# shrew-mini.net
KiCad netlist of a schematic drawn in EAGLE
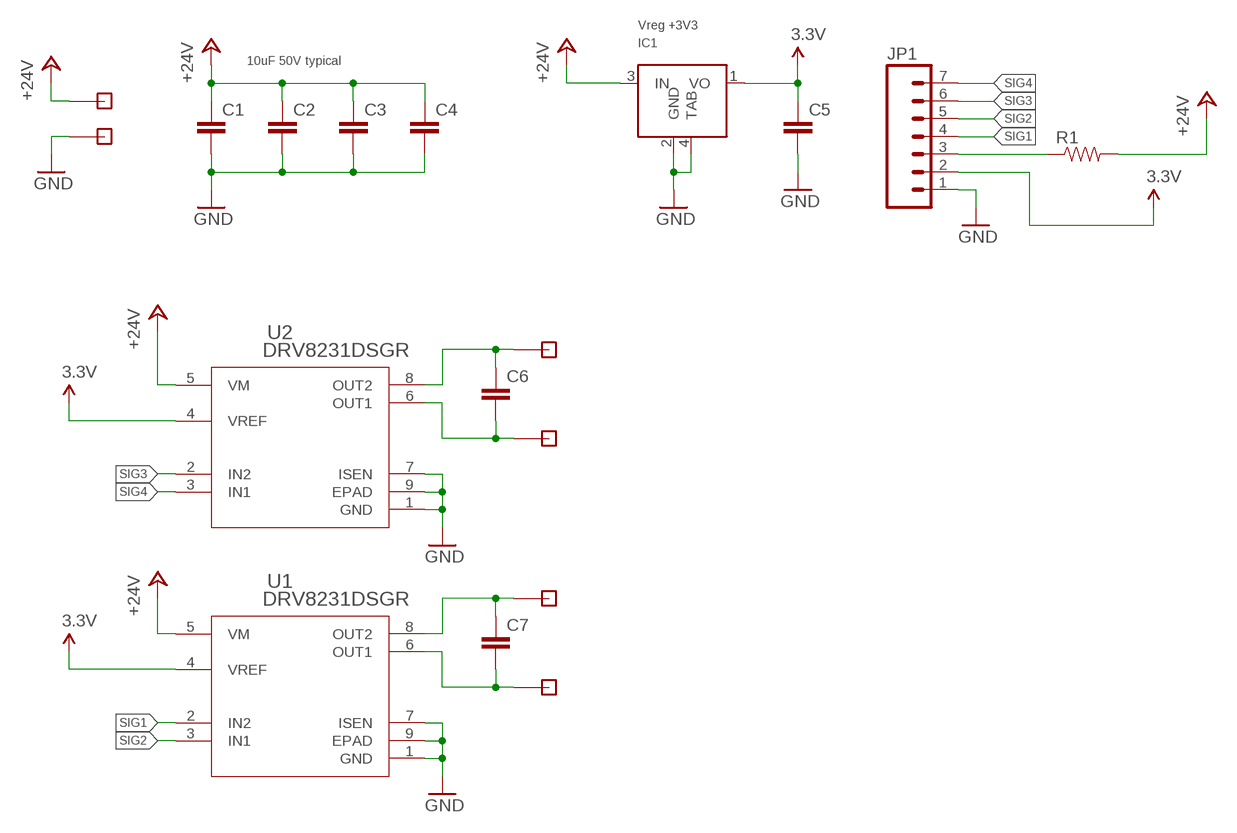
[diagram p0: schematic, sheet 1]

(export (version "E")
  (design (tool "Eeschema 10.0.6"))
  (components
    (comp (ref "C1")
      (value "CAP0805")
      (footprint "eagle-import:0805")
      (libsource (lib "eagle-import") (part "CAP0805"))
    )
    (comp (ref "C2")
      (value "CAP0805")
      (footprint "eagle-import:0805")
      (libsource (lib "eagle-import") (part "CAP0805"))
    )
    (comp (ref "C3")
      (value "CAP0805")
      (footprint "eagle-import:0805")
      (libsource (lib "eagle-import") (part "CAP0805"))
    )
    (comp (ref "C4")
      (value "CAP0805")
      (footprint "eagle-import:0805")
      (libsource (lib "eagle-import") (part "CAP0805"))
    )
    (comp (ref "C5")
      (value "CAP0805")
      (footprint "eagle-import:0805")
      (libsource (lib "eagle-import") (part "CAP0805"))
    )
    (comp (ref "C6")
      (value "CAP0402-CAP")
      (footprint "eagle-import:0402-CAP")
      (libsource (lib "eagle-import") (part "CAP0402-CAP"))
    )
    (comp (ref "C7")
      (value "CAP0402-CAP")
      (footprint "eagle-import:0402-CAP")
      (libsource (lib "eagle-import") (part "CAP0402-CAP"))
    )
    (comp (ref "IC1")
      (value "Vreg +3V3")
      (footprint "eagle-import:SOT89")
      (libsource (lib "eagle-import") (part "V_REG_SOT89-SOT89"))
    )
    (comp (ref "JP1")
      (value "M07-2MM-TH")
      (footprint "eagle-import:1X07-2MM-TH")
      (libsource (lib "eagle-import") (part "M07-2MM-TH"))
    )
    (comp (ref "R1")
      (value "RESISTOR0402-RES")
      (footprint "eagle-import:0402-RES")
      (libsource (lib "eagle-import") (part "RESISTOR0402-RES"))
    )
    (comp (ref "U1")
      (value "DRV8231DSGR")
      (footprint "eagle-import:WSON8_DRV8231_TEX")
      (fields (field (name "COPYRIGHT") "Copyright (C) 2024 Ultra Librarian. All rights reserved."))
      (libsource (lib "eagle-import") (part "DRV8231DSGR"))
    )
    (comp (ref "U2")
      (value "DRV8231DSGR")
      (footprint "eagle-import:WSON8_DRV8231_TEX")
      (fields (field (name "COPYRIGHT") "Copyright (C) 2024 Ultra Librarian. All rights reserved."))
      (libsource (lib "eagle-import") (part "DRV8231DSGR"))
    )
    (comp (ref "X1")
      (value "PIN-1X-BIG")
      (footprint "eagle-import:PAD-1X-BIG")
      (libsource (lib "eagle-import") (part "PIN-1X-BIG"))
    )
    (comp (ref "X2")
      (value "PIN-1X-BIG")
      (footprint "eagle-import:PAD-1X-BIG")
      (libsource (lib "eagle-import") (part "PIN-1X-BIG"))
    )
    (comp (ref "X3")
      (value "PIN-1X-BIG")
      (footprint "eagle-import:PAD-1X-BIG")
      (libsource (lib "eagle-import") (part "PIN-1X-BIG"))
    )
    (comp (ref "X4")
      (value "PIN-1X-BIG")
      (footprint "eagle-import:PAD-1X-BIG")
      (libsource (lib "eagle-import") (part "PIN-1X-BIG"))
    )
    (comp (ref "X5")
      (value "PIN-1X-1.5MMSQ")
      (footprint "eagle-import:PAD-1X-1.5MMSQ")
      (libsource (lib "eagle-import") (part "PIN-1X-1.5MMSQ"))
    )
    (comp (ref "X6")
      (value "PIN-1X-MED")
      (footprint "eagle-import:PAD-1X-MED")
      (libsource (lib "eagle-import") (part "PIN-1X-MED"))
    )
  )
  (nets
    (net (code "1") (name "+24V") (class "Default")
      (node (ref "C1") (pin "1") (pinfunction "1_1") (pintype "passive"))
      (node (ref "C2") (pin "1") (pinfunction "1_1") (pintype "passive"))
      (node (ref "C3") (pin "1") (pinfunction "1_1") (pintype "passive"))
      (node (ref "C4") (pin "1") (pinfunction "1_1") (pintype "passive"))
      (node (ref "IC1") (pin "3") (pinfunction "IN_3") (pintype "input"))
      (node (ref "R1") (pin "2") (pinfunction "2_2") (pintype "passive"))
      (node (ref "U1") (pin "5") (pinfunction "VM_5") (pintype "input"))
      (node (ref "U2") (pin "5") (pinfunction "VM_5") (pintype "input"))
      (node (ref "X5") (pin "P$1") (pinfunction "P$1_P$1") (pintype "bidirectional"))
    )
    (net (code "2") (name "3.3V") (class "Default")
      (node (ref "C5") (pin "1") (pinfunction "1_1") (pintype "passive"))
      (node (ref "IC1") (pin "1") (pinfunction "VO_1") (pintype "output"))
      (node (ref "JP1") (pin "2") (pinfunction "2_2") (pintype "passive"))
      (node (ref "U1") (pin "4") (pinfunction "VREF_4") (pintype "input"))
      (node (ref "U2") (pin "4") (pinfunction "VREF_4") (pintype "input"))
    )
    (net (code "3") (name "GND") (class "Default")
      (node (ref "C1") (pin "2") (pinfunction "2_2") (pintype "passive"))
      (node (ref "C2") (pin "2") (pinfunction "2_2") (pintype "passive"))
      (node (ref "C3") (pin "2") (pinfunction "2_2") (pintype "passive"))
      (node (ref "C4") (pin "2") (pinfunction "2_2") (pintype "passive"))
      (node (ref "C5") (pin "2") (pinfunction "2_2") (pintype "passive"))
      (node (ref "IC1") (pin "2") (pinfunction "GND_2") (pintype "input"))
      (node (ref "IC1") (pin "4") (pinfunction "TAB_4") (pintype "input"))
      (node (ref "JP1") (pin "1") (pinfunction "1_1") (pintype "passive"))
      (node (ref "U1") (pin "1") (pinfunction "GND_1") (pintype "input"))
      (node (ref "U1") (pin "7") (pinfunction "ISEN_7") (pintype "input"))
      (node (ref "U1") (pin "9") (pinfunction "EPAD_9") (pintype "input"))
      (node (ref "U2") (pin "1") (pinfunction "GND_1") (pintype "input"))
      (node (ref "U2") (pin "7") (pinfunction "ISEN_7") (pintype "input"))
      (node (ref "U2") (pin "9") (pinfunction "EPAD_9") (pintype "input"))
      (node (ref "X6") (pin "P$1") (pinfunction "P$1_P$1") (pintype "bidirectional"))
    )
    (net (code "4") (name "Net-(JP1-Pad3)") (class "Default")
      (node (ref "JP1") (pin "3") (pinfunction "3_3") (pintype "passive"))
      (node (ref "R1") (pin "1") (pinfunction "1_1") (pintype "passive"))
    )
    (net (code "5") (name "Net-(U1-OUT1)") (class "Default")
      (node (ref "C7") (pin "2") (pinfunction "2_2") (pintype "passive"))
      (node (ref "U1") (pin "6") (pinfunction "OUT1_6") (pintype "output"))
      (node (ref "X3") (pin "1") (pinfunction "P$1_1") (pintype "bidirectional"))
    )
    (net (code "6") (name "Net-(U1-OUT2)") (class "Default")
      (node (ref "C7") (pin "1") (pinfunction "1_1") (pintype "passive"))
      (node (ref "U1") (pin "8") (pinfunction "OUT2_8") (pintype "output"))
      (node (ref "X4") (pin "1") (pinfunction "P$1_1") (pintype "bidirectional"))
    )
    (net (code "7") (name "Net-(U2-OUT1)") (class "Default")
      (node (ref "C6") (pin "2") (pinfunction "2_2") (pintype "passive"))
      (node (ref "U2") (pin "6") (pinfunction "OUT1_6") (pintype "output"))
      (node (ref "X1") (pin "1") (pinfunction "P$1_1") (pintype "bidirectional"))
    )
    (net (code "8") (name "Net-(U2-OUT2)") (class "Default")
      (node (ref "C6") (pin "1") (pinfunction "1_1") (pintype "passive"))
      (node (ref "U2") (pin "8") (pinfunction "OUT2_8") (pintype "output"))
      (node (ref "X2") (pin "1") (pinfunction "P$1_1") (pintype "bidirectional"))
    )
    (net (code "9") (name "SIG1") (class "Default")
      (node (ref "JP1") (pin "4") (pinfunction "4_4") (pintype "passive"))
      (node (ref "U1") (pin "2") (pinfunction "IN2_2") (pintype "input"))
    )
    (net (code "10") (name "SIG2") (class "Default")
      (node (ref "JP1") (pin "5") (pinfunction "5_5") (pintype "passive"))
      (node (ref "U1") (pin "3") (pinfunction "IN1_3") (pintype "input"))
    )
    (net (code "11") (name "SIG3") (class "Default")
      (node (ref "JP1") (pin "6") (pinfunction "6_6") (pintype "passive"))
      (node (ref "U2") (pin "2") (pinfunction "IN2_2") (pintype "input"))
    )
    (net (code "12") (name "SIG4") (class "Default")
      (node (ref "JP1") (pin "7") (pinfunction "7_7") (pintype "passive"))
      (node (ref "U2") (pin "3") (pinfunction "IN1_3") (pintype "input"))
    )
  )
)
